# 8-Bit_Instruction_Register_Part_2.net
KiCad netlist of a schematic drawn in EAGLE
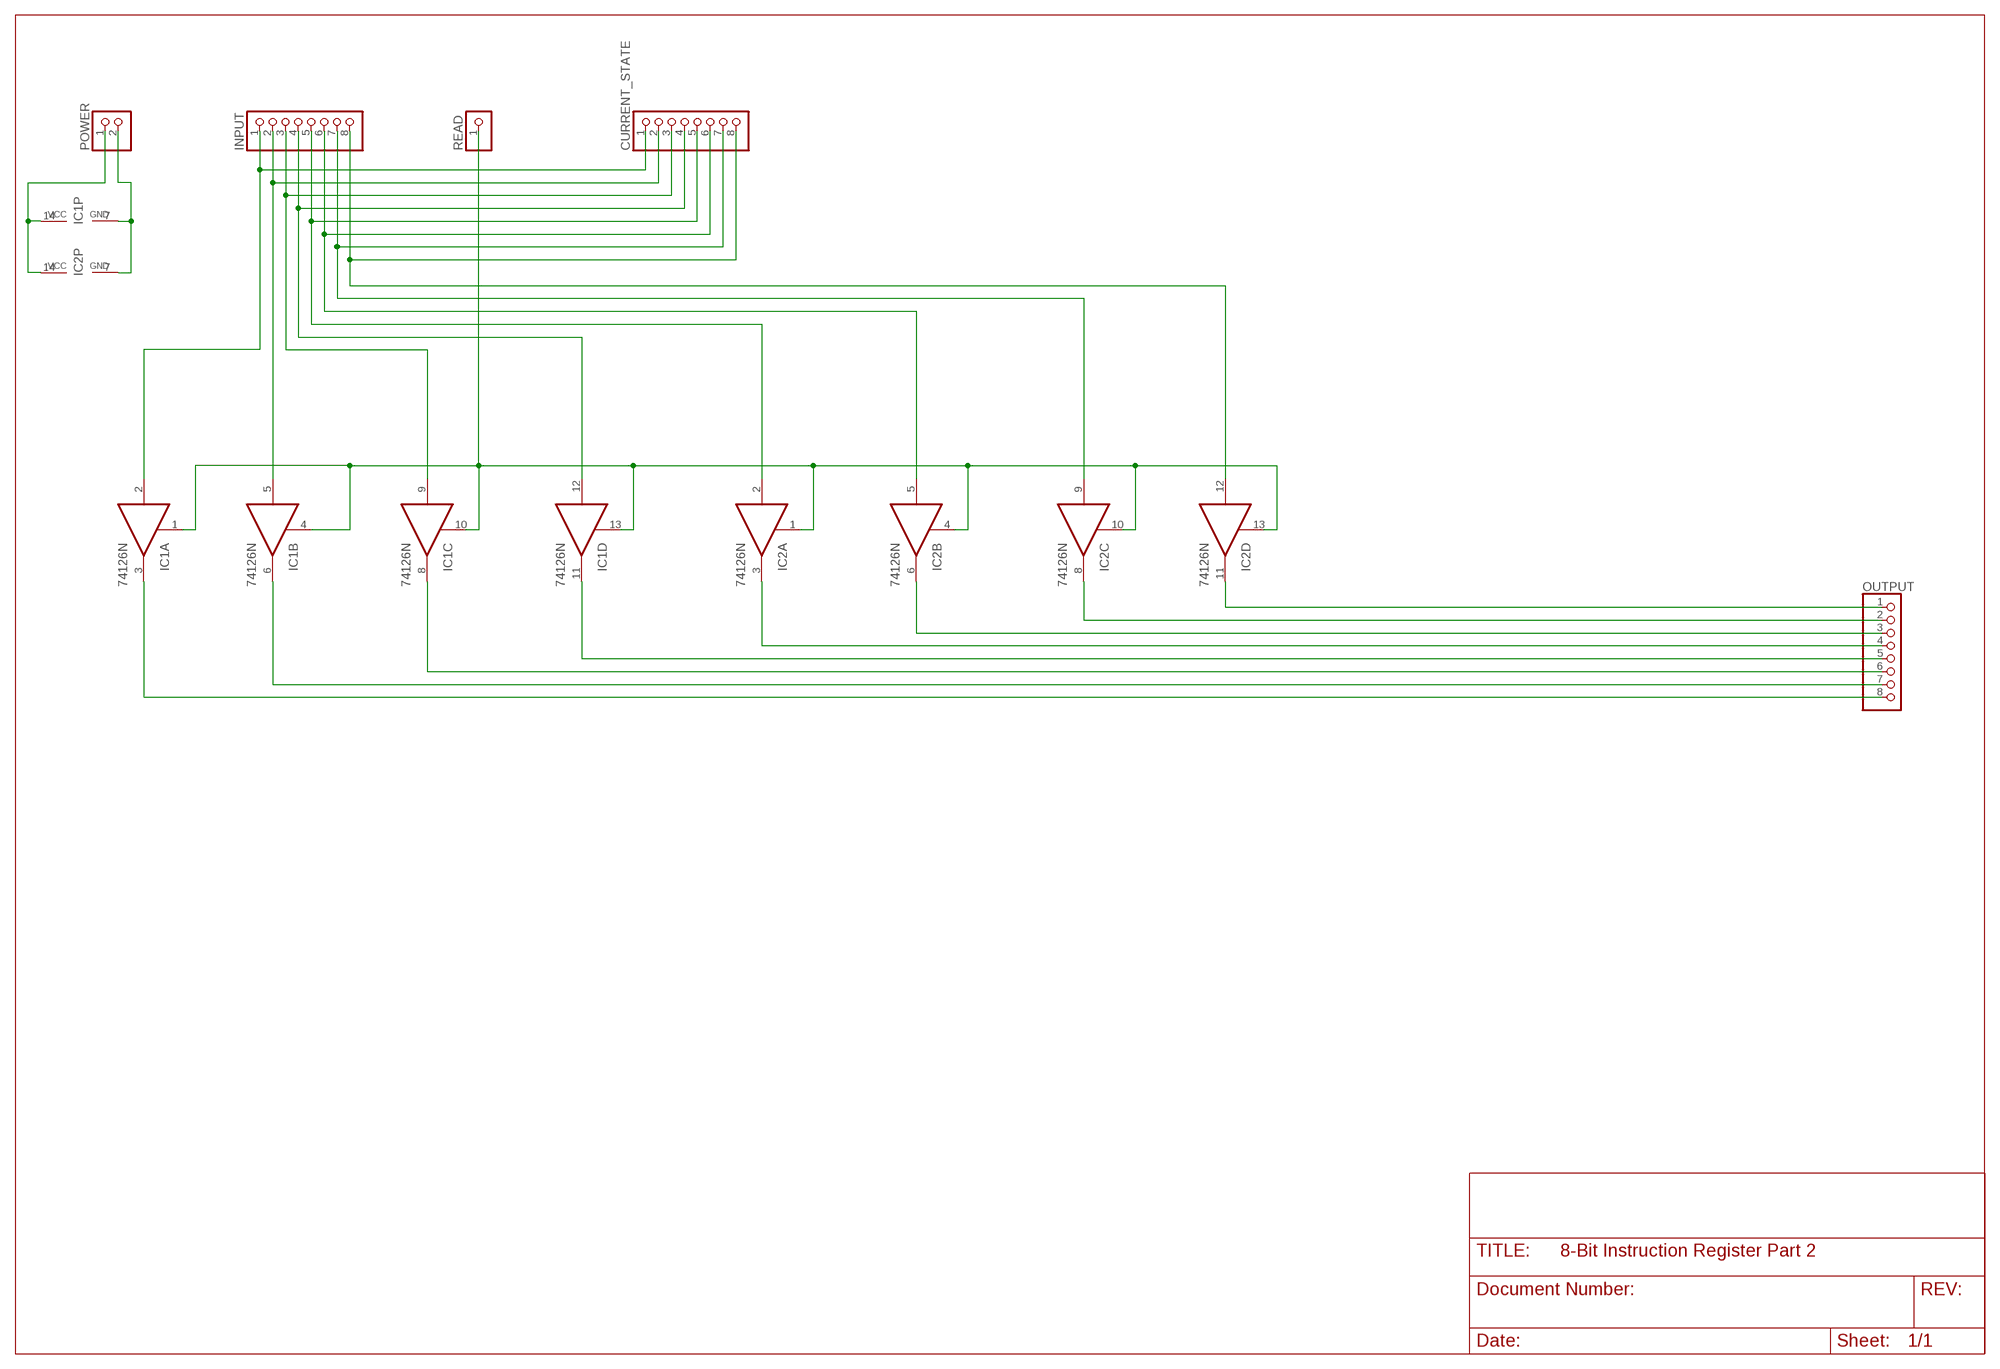
[diagram p0: schematic, sheet 1]

(export (version "E")
  (design (tool "Eeschema 10.0.6"))
  (components
    (comp (ref "CURRENT_STATE")
      (value "PINHD-1X8")
      (footprint "eagle-import:1X08")
      (libsource (lib "eagle-import") (part "PINHD-1X8"))
    )
    (comp (ref "IC1")
      (value "74126N")
      (footprint "eagle-import:DIL14")
      (libsource (lib "eagle-import") (part "74126N"))
    )
    (comp (ref "IC2")
      (value "74126N")
      (footprint "eagle-import:DIL14")
      (libsource (lib "eagle-import") (part "74126N"))
    )
    (comp (ref "INPUT")
      (value "PINHD-1X8")
      (footprint "eagle-import:1X08")
      (libsource (lib "eagle-import") (part "PINHD-1X8"))
    )
    (comp (ref "OUTPUT")
      (value "PINHD-1X8")
      (footprint "eagle-import:1X08")
      (libsource (lib "eagle-import") (part "PINHD-1X8"))
    )
    (comp (ref "POWER")
      (value "PINHD-1X2")
      (footprint "eagle-import:1X02")
      (libsource (lib "eagle-import") (part "PINHD-1X2"))
    )
    (comp (ref "READ")
      (value "PINHD-1X1")
      (footprint "eagle-import:1X01")
      (libsource (lib "eagle-import") (part "PINHD-1X1"))
    )
  )
  (nets
    (net (code "1") (name "Net-(IC1A-I)") (class "Default")
      (node (ref "CURRENT_STATE") (pin "1") (pinfunction "1_1") (pintype "passive"))
      (node (ref "IC1") (pin "2") (pinfunction "I_2") (pintype "input"))
      (node (ref "INPUT") (pin "1") (pinfunction "1_1") (pintype "passive"))
    )
    (net (code "2") (name "Net-(IC1A-O)") (class "Default")
      (node (ref "IC1") (pin "3") (pinfunction "O_3") (pintype "output"))
      (node (ref "OUTPUT") (pin "8") (pinfunction "8_8") (pintype "passive"))
    )
    (net (code "3") (name "Net-(IC1A-OE)") (class "Default")
      (node (ref "IC1") (pin "1") (pinfunction "OE_1") (pintype "input"))
      (node (ref "IC1") (pin "10") (pinfunction "OE_10") (pintype "input"))
      (node (ref "IC1") (pin "13") (pinfunction "OE_13") (pintype "input"))
      (node (ref "IC1") (pin "4") (pinfunction "OE_4") (pintype "input"))
      (node (ref "IC2") (pin "1") (pinfunction "OE_1") (pintype "input"))
      (node (ref "IC2") (pin "10") (pinfunction "OE_10") (pintype "input"))
      (node (ref "IC2") (pin "13") (pinfunction "OE_13") (pintype "input"))
      (node (ref "IC2") (pin "4") (pinfunction "OE_4") (pintype "input"))
      (node (ref "READ") (pin "1") (pinfunction "1_1") (pintype "passive"))
    )
    (net (code "4") (name "Net-(IC1B-I)") (class "Default")
      (node (ref "CURRENT_STATE") (pin "2") (pinfunction "2_2") (pintype "passive"))
      (node (ref "IC1") (pin "5") (pinfunction "I_5") (pintype "input"))
      (node (ref "INPUT") (pin "2") (pinfunction "2_2") (pintype "passive"))
    )
    (net (code "5") (name "Net-(IC1B-O)") (class "Default")
      (node (ref "IC1") (pin "6") (pinfunction "O_6") (pintype "output"))
      (node (ref "OUTPUT") (pin "7") (pinfunction "7_7") (pintype "passive"))
    )
    (net (code "6") (name "Net-(IC1C-I)") (class "Default")
      (node (ref "CURRENT_STATE") (pin "3") (pinfunction "3_3") (pintype "passive"))
      (node (ref "IC1") (pin "9") (pinfunction "I_9") (pintype "input"))
      (node (ref "INPUT") (pin "3") (pinfunction "3_3") (pintype "passive"))
    )
    (net (code "7") (name "Net-(IC1C-O)") (class "Default")
      (node (ref "IC1") (pin "8") (pinfunction "O_8") (pintype "output"))
      (node (ref "OUTPUT") (pin "6") (pinfunction "6_6") (pintype "passive"))
    )
    (net (code "8") (name "Net-(IC1D-I)") (class "Default")
      (node (ref "CURRENT_STATE") (pin "4") (pinfunction "4_4") (pintype "passive"))
      (node (ref "IC1") (pin "12") (pinfunction "I_12") (pintype "input"))
      (node (ref "INPUT") (pin "4") (pinfunction "4_4") (pintype "passive"))
    )
    (net (code "9") (name "Net-(IC1D-O)") (class "Default")
      (node (ref "IC1") (pin "11") (pinfunction "O_11") (pintype "output"))
      (node (ref "OUTPUT") (pin "5") (pinfunction "5_5") (pintype "passive"))
    )
    (net (code "10") (name "Net-(IC1E-GND)") (class "Default")
      (node (ref "IC1") (pin "7") (pinfunction "GND_7") (pintype "power_in"))
      (node (ref "IC2") (pin "7") (pinfunction "GND_7") (pintype "power_in"))
      (node (ref "POWER") (pin "2") (pinfunction "2_2") (pintype "passive"))
    )
    (net (code "11") (name "Net-(IC1E-VCC)") (class "Default")
      (node (ref "IC1") (pin "14") (pinfunction "VCC_14") (pintype "power_in"))
      (node (ref "IC2") (pin "14") (pinfunction "VCC_14") (pintype "power_in"))
      (node (ref "POWER") (pin "1") (pinfunction "1_1") (pintype "passive"))
    )
    (net (code "12") (name "Net-(IC2A-I)") (class "Default")
      (node (ref "CURRENT_STATE") (pin "5") (pinfunction "5_5") (pintype "passive"))
      (node (ref "IC2") (pin "2") (pinfunction "I_2") (pintype "input"))
      (node (ref "INPUT") (pin "5") (pinfunction "5_5") (pintype "passive"))
    )
    (net (code "13") (name "Net-(IC2A-O)") (class "Default")
      (node (ref "IC2") (pin "3") (pinfunction "O_3") (pintype "output"))
      (node (ref "OUTPUT") (pin "4") (pinfunction "4_4") (pintype "passive"))
    )
    (net (code "14") (name "Net-(IC2B-I)") (class "Default")
      (node (ref "CURRENT_STATE") (pin "6") (pinfunction "6_6") (pintype "passive"))
      (node (ref "IC2") (pin "5") (pinfunction "I_5") (pintype "input"))
      (node (ref "INPUT") (pin "6") (pinfunction "6_6") (pintype "passive"))
    )
    (net (code "15") (name "Net-(IC2B-O)") (class "Default")
      (node (ref "IC2") (pin "6") (pinfunction "O_6") (pintype "output"))
      (node (ref "OUTPUT") (pin "3") (pinfunction "3_3") (pintype "passive"))
    )
    (net (code "16") (name "Net-(IC2C-I)") (class "Default")
      (node (ref "CURRENT_STATE") (pin "7") (pinfunction "7_7") (pintype "passive"))
      (node (ref "IC2") (pin "9") (pinfunction "I_9") (pintype "input"))
      (node (ref "INPUT") (pin "7") (pinfunction "7_7") (pintype "passive"))
    )
    (net (code "17") (name "Net-(IC2C-O)") (class "Default")
      (node (ref "IC2") (pin "8") (pinfunction "O_8") (pintype "output"))
      (node (ref "OUTPUT") (pin "2") (pinfunction "2_2") (pintype "passive"))
    )
    (net (code "18") (name "Net-(IC2D-I)") (class "Default")
      (node (ref "CURRENT_STATE") (pin "8") (pinfunction "8_8") (pintype "passive"))
      (node (ref "IC2") (pin "12") (pinfunction "I_12") (pintype "input"))
      (node (ref "INPUT") (pin "8") (pinfunction "8_8") (pintype "passive"))
    )
    (net (code "19") (name "Net-(IC2D-O)") (class "Default")
      (node (ref "IC2") (pin "11") (pinfunction "O_11") (pintype "output"))
      (node (ref "OUTPUT") (pin "1") (pinfunction "1_1") (pintype "passive"))
    )
  )
)
